# plugV15-smd.net
KiCad netlist of a schematic drawn in EAGLE
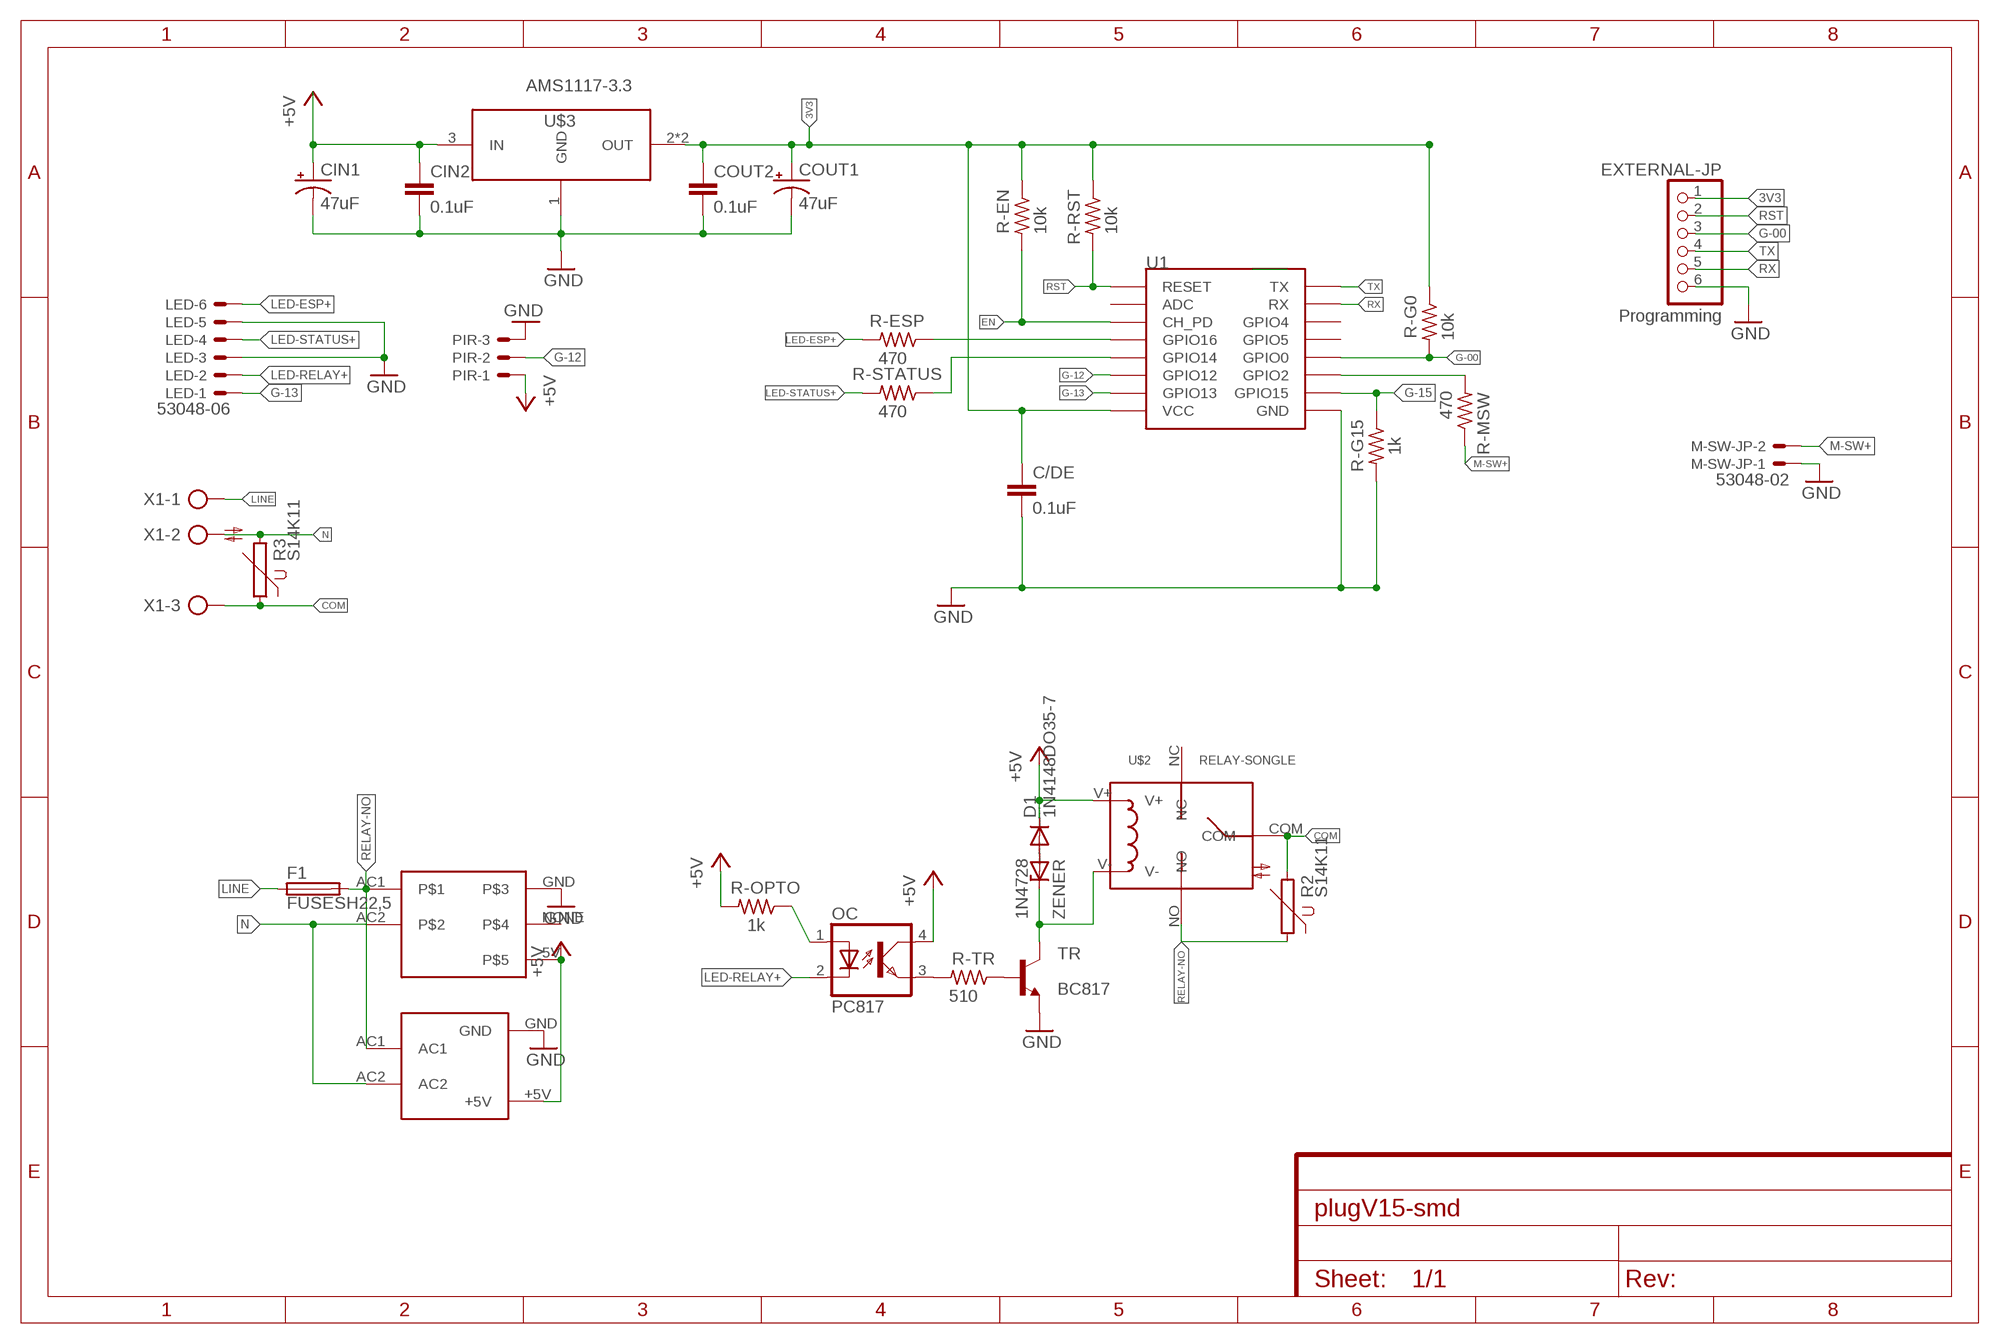
[diagram p0: schematic, sheet 1]

(export (version "E")
  (design (tool "Eeschema 10.0.6"))
  (components
    (comp (ref "C/DE")
      (value "0.1uF")
      (footprint "eagle-import:C0805")
      (libsource (lib "eagle-import") (part "C-EUC0805"))
    )
    (comp (ref "CIN1")
      (value "47uF")
      (footprint "eagle-import:E2,5-5")
      (libsource (lib "eagle-import") (part "CPOL-USE2.5-5"))
    )
    (comp (ref "CIN2")
      (value "0.1uF")
      (footprint "eagle-import:C0805")
      (libsource (lib "eagle-import") (part "C-EUC0805"))
    )
    (comp (ref "COUT1")
      (value "47uF")
      (footprint "eagle-import:E2,5-5")
      (libsource (lib "eagle-import") (part "CPOL-USE2.5-5"))
    )
    (comp (ref "COUT2")
      (value "0.1uF")
      (footprint "eagle-import:C0805")
      (libsource (lib "eagle-import") (part "C-EUC0805"))
    )
    (comp (ref "D1")
      (value "1N4148DO35-7")
      (footprint "eagle-import:DO35-7")
      (libsource (lib "eagle-import") (part "1N4148DO35-7"))
    )
    (comp (ref "EXTERNAL-JP")
      (value "Programming")
      (footprint "eagle-import:1X06")
      (libsource (lib "eagle-import") (part "PINHD-1X6"))
    )
    (comp (ref "F1")
      (value "FUSESH22,5")
      (footprint "eagle-import:SH22,5")
      (libsource (lib "eagle-import") (part "FUSESH22,5"))
    )
    (comp (ref "LED")
      (value "53048-06")
      (footprint "eagle-import:53048-06")
      (fields (field (name "MF") "WALDOM/MOLEX") (field (name "MPN") "53048-0610"))
      (libsource (lib "eagle-import") (part "53?-06048"))
    )
    (comp (ref "M-SW-JP")
      (value "53048-02")
      (footprint "eagle-import:53048-02")
      (fields (field (name "MF") "MOLEX") (field (name "MPN") "53048-0210"))
      (libsource (lib "eagle-import") (part "53?-02048"))
    )
    (comp (ref "OC")
      (value "PC817")
      (footprint "eagle-import:DIL04")
      (fields (field (name "MPN") "PC817X4J000F"))
      (libsource (lib "eagle-import") (part "PC817"))
    )
    (comp (ref "PIR")
      (value "53048-03")
      (footprint "eagle-import:53048-03")
      (fields (field (name "MF") "WALDOM/MOLEX") (field (name "MPN") "53048-0310"))
      (libsource (lib "eagle-import") (part "53?-03048"))
    )
    (comp (ref "R-EN")
      (value "10k")
      (footprint "eagle-import:M0805")
      (libsource (lib "eagle-import") (part "R-US_M0805"))
    )
    (comp (ref "R-ESP")
      (value "470")
      (footprint "eagle-import:M0805")
      (libsource (lib "eagle-import") (part "R-US_M0805"))
    )
    (comp (ref "R-G0")
      (value "10k")
      (footprint "eagle-import:M0805")
      (libsource (lib "eagle-import") (part "R-US_M0805"))
    )
    (comp (ref "R-G15")
      (value "1k")
      (footprint "eagle-import:M0805")
      (libsource (lib "eagle-import") (part "R-US_M0805"))
    )
    (comp (ref "R-MSW")
      (value "470")
      (footprint "eagle-import:M0805")
      (libsource (lib "eagle-import") (part "R-US_M0805"))
    )
    (comp (ref "R-OPTO")
      (value "1k")
      (footprint "eagle-import:M0805")
      (libsource (lib "eagle-import") (part "R-US_M0805"))
    )
    (comp (ref "R-RST")
      (value "10k")
      (footprint "eagle-import:M0805")
      (libsource (lib "eagle-import") (part "R-US_M0805"))
    )
    (comp (ref "R-STATUS")
      (value "470")
      (footprint "eagle-import:M0805")
      (libsource (lib "eagle-import") (part "R-US_M0805"))
    )
    (comp (ref "R-TR")
      (value "510")
      (footprint "eagle-import:M0805")
      (libsource (lib "eagle-import") (part "R-US_M0805"))
    )
    (comp (ref "R2")
      (value "S14K11")
      (footprint "eagle-import:S14K11")
      (libsource (lib "eagle-import") (part "S14K11"))
    )
    (comp (ref "R3")
      (value "S14K11")
      (footprint "eagle-import:S14K11")
      (libsource (lib "eagle-import") (part "S14K11"))
    )
    (comp (ref "TR")
      (value "BC817")
      (footprint "eagle-import:SOT23-BEC")
      (libsource (lib "eagle-import") (part "BC817SMD-16"))
    )
    (comp (ref "U$1")
      (value "HLK-PM01")
      (footprint "eagle-import:HLK-PM01")
      (libsource (lib "eagle-import") (part "HLK-PM01"))
    )
    (comp (ref "U$2")
      (value "RELAY-SONGLE")
      (footprint "eagle-import:RELAY-SONGLE")
      (libsource (lib "eagle-import") (part "RELAY-SONGLE"))
    )
    (comp (ref "U$3")
      (value "AMS1117-3.3")
      (footprint "eagle-import:SOT-223")
      (libsource (lib "eagle-import") (part "AMS1117-3.3"))
    )
    (comp (ref "U$4")
      (value "POWERSUPPLY-5V-700MA")
      (footprint "eagle-import:POWERSUPPLY-5V-700MA")
      (libsource (lib "eagle-import") (part "POWERSUPPLY-5V-700MA"))
    )
    (comp (ref "U1")
      (value "ESP12SMD")
      (footprint "eagle-import:ESP12-SMD")
      (libsource (lib "eagle-import") (part "ESP12SMD"))
    )
    (comp (ref "X1")
      (value "AK300/3")
      (footprint "eagle-import:AK300_3")
      (libsource (lib "eagle-import") (part "AK300/3"))
    )
    (comp (ref "ZENER")
      (value "1N4728")
      (footprint "eagle-import:DO41Z10")
      (libsource (lib "eagle-import") (part "1N4728"))
    )
  )
  (nets
    (net (code "1") (name "+5V") (class "Default")
      (node (ref "CIN1") (pin "+") (pinfunction "+_+") (pintype "passive"))
      (node (ref "CIN2") (pin "1") (pinfunction "1_1") (pintype "passive"))
      (node (ref "D1") (pin "C") (pinfunction "C_C") (pintype "passive"))
      (node (ref "OC") (pin "4") (pinfunction "COL_4") (pintype "passive"))
      (node (ref "PIR") (pin "1") (pinfunction "S_1") (pintype "passive"))
      (node (ref "R-OPTO") (pin "2") (pinfunction "2_2") (pintype "passive"))
      (node (ref "U$1") (pin "+5V") (pinfunction "+5V_+5V") (pintype "bidirectional"))
      (node (ref "U$2") (pin "V+") (pinfunction "V+_V+") (pintype "bidirectional"))
      (node (ref "U$3") (pin "3") (pinfunction "IN_3") (pintype "input"))
      (node (ref "U$4") (pin "5V") (pinfunction "P$5_5V") (pintype "bidirectional"))
    )
    (net (code "2") (name "3V3") (class "Default")
      (node (ref "C/DE") (pin "1") (pinfunction "1_1") (pintype "passive"))
      (node (ref "COUT1") (pin "+") (pinfunction "+_+") (pintype "passive"))
      (node (ref "COUT2") (pin "1") (pinfunction "1_1") (pintype "passive"))
      (node (ref "EXTERNAL-JP") (pin "1") (pinfunction "1_1") (pintype "passive"))
      (node (ref "R-EN") (pin "1") (pinfunction "1_1") (pintype "passive"))
      (node (ref "R-G0") (pin "1") (pinfunction "1_1") (pintype "passive"))
      (node (ref "R-RST") (pin "1") (pinfunction "1_1") (pintype "passive"))
      (node (ref "U$3") (pin "2") (pinfunction "OUT_2") (pintype "output"))
      (node (ref "U$3") (pin "4") (pinfunction "OUT_4") (pintype "output"))
      (node (ref "U1") (pin "VCC") (pinfunction "VCC_VCC") (pintype "bidirectional"))
    )
    (net (code "3") (name "COM") (class "Default")
      (node (ref "R2") (pin "2") (pinfunction "2_2") (pintype "passive"))
      (node (ref "R3") (pin "1") (pinfunction "1_1") (pintype "passive"))
      (node (ref "U$2") (pin "COM") (pinfunction "COM_COM") (pintype "bidirectional"))
      (node (ref "X1") (pin "3") (pinfunction "KL_3") (pintype "passive"))
    )
    (net (code "4") (name "EN") (class "Default")
      (node (ref "R-EN") (pin "2") (pinfunction "2_2") (pintype "passive"))
      (node (ref "U1") (pin "CH_PD") (pinfunction "CH_PD_CH_PD") (pintype "bidirectional"))
    )
    (net (code "5") (name "G-00") (class "Default")
      (node (ref "EXTERNAL-JP") (pin "3") (pinfunction "3_3") (pintype "passive"))
      (node (ref "R-G0") (pin "2") (pinfunction "2_2") (pintype "passive"))
      (node (ref "U1") (pin "GPIO0") (pinfunction "GPIO0_GPIO0") (pintype "bidirectional"))
    )
    (net (code "6") (name "G-12") (class "Default")
      (node (ref "PIR") (pin "2") (pinfunction "S_2") (pintype "passive"))
      (node (ref "U1") (pin "GPIO12") (pinfunction "GPIO12_GPIO12") (pintype "bidirectional"))
    )
    (net (code "7") (name "G-13") (class "Default")
      (node (ref "LED") (pin "1") (pinfunction "S_1") (pintype "passive"))
      (node (ref "U1") (pin "GPIO13") (pinfunction "GPIO13_GPIO13") (pintype "bidirectional"))
    )
    (net (code "8") (name "G-15") (class "Default")
      (node (ref "R-G15") (pin "1") (pinfunction "1_1") (pintype "passive"))
      (node (ref "U1") (pin "GPIO15") (pinfunction "GPIO15_GPIO15") (pintype "bidirectional"))
    )
    (net (code "9") (name "GND") (class "Default")
      (node (ref "C/DE") (pin "2") (pinfunction "2_2") (pintype "passive"))
      (node (ref "CIN1") (pin "-") (pinfunction "-_-") (pintype "passive"))
      (node (ref "CIN2") (pin "2") (pinfunction "2_2") (pintype "passive"))
      (node (ref "COUT1") (pin "-") (pinfunction "-_-") (pintype "passive"))
      (node (ref "COUT2") (pin "2") (pinfunction "2_2") (pintype "passive"))
      (node (ref "EXTERNAL-JP") (pin "6") (pinfunction "6_6") (pintype "passive"))
      (node (ref "LED") (pin "3") (pinfunction "S_3") (pintype "passive"))
      (node (ref "LED") (pin "5") (pinfunction "S_5") (pintype "passive"))
      (node (ref "M-SW-JP") (pin "1") (pinfunction "S_1") (pintype "passive"))
      (node (ref "PIR") (pin "3") (pinfunction "S_3") (pintype "passive"))
      (node (ref "R-G15") (pin "2") (pinfunction "2_2") (pintype "passive"))
      (node (ref "TR") (pin "E") (pinfunction "E_E") (pintype "passive"))
      (node (ref "U$1") (pin "GND") (pinfunction "GND_GND") (pintype "bidirectional"))
      (node (ref "U$3") (pin "1") (pinfunction "GND_1") (pintype "passive"))
      (node (ref "U$4") (pin "GND") (pinfunction "P$3_GND") (pintype "bidirectional"))
      (node (ref "U1") (pin "GND") (pinfunction "GND_GND") (pintype "bidirectional"))
    )
    (net (code "10") (name "LED-ESP+") (class "Default")
      (node (ref "LED") (pin "6") (pinfunction "S_6") (pintype "passive"))
      (node (ref "R-ESP") (pin "2") (pinfunction "2_2") (pintype "passive"))
    )
    (net (code "11") (name "LED-RELAY+") (class "Default")
      (node (ref "LED") (pin "2") (pinfunction "S_2") (pintype "passive"))
      (node (ref "OC") (pin "2") (pinfunction "C_2") (pintype "passive"))
    )
    (net (code "12") (name "LED-STATUS+") (class "Default")
      (node (ref "LED") (pin "4") (pinfunction "S_4") (pintype "passive"))
      (node (ref "R-STATUS") (pin "2") (pinfunction "2_2") (pintype "passive"))
    )
    (net (code "13") (name "LINE") (class "Default")
      (node (ref "F1") (pin "1") (pinfunction "1_1") (pintype "passive"))
      (node (ref "X1") (pin "1") (pinfunction "KL_1") (pintype "passive"))
    )
    (net (code "14") (name "M-SW+") (class "Default")
      (node (ref "M-SW-JP") (pin "2") (pinfunction "S_2") (pintype "passive"))
      (node (ref "R-MSW") (pin "1") (pinfunction "1_1") (pintype "passive"))
    )
    (net (code "15") (name "N") (class "Default")
      (node (ref "R3") (pin "2") (pinfunction "2_2") (pintype "passive"))
      (node (ref "U$1") (pin "AC2") (pinfunction "AC2_AC2") (pintype "bidirectional"))
      (node (ref "U$4") (pin "AC2") (pinfunction "P$2_AC2") (pintype "bidirectional"))
      (node (ref "X1") (pin "2") (pinfunction "KL_2") (pintype "passive"))
    )
    (net (code "16") (name "Net-(D1-PadA)") (class "Default")
      (node (ref "D1") (pin "A") (pinfunction "A_A") (pintype "passive"))
      (node (ref "ZENER") (pin "A") (pinfunction "A_A") (pintype "passive"))
    )
    (net (code "17") (name "Net-(OC-A)") (class "Default")
      (node (ref "OC") (pin "1") (pinfunction "A_1") (pintype "passive"))
      (node (ref "R-OPTO") (pin "1") (pinfunction "1_1") (pintype "passive"))
    )
    (net (code "18") (name "Net-(OC-EMIT)") (class "Default")
      (node (ref "OC") (pin "3") (pinfunction "EMIT_3") (pintype "passive"))
      (node (ref "R-TR") (pin "2") (pinfunction "2_2") (pintype "passive"))
    )
    (net (code "19") (name "Net-(R-ESP-Pad1)") (class "Default")
      (node (ref "R-ESP") (pin "1") (pinfunction "1_1") (pintype "passive"))
      (node (ref "U1") (pin "GPIO16") (pinfunction "GPIO16_GPIO16") (pintype "bidirectional"))
    )
    (net (code "20") (name "Net-(R-MSW-Pad2)") (class "Default")
      (node (ref "R-MSW") (pin "2") (pinfunction "2_2") (pintype "passive"))
      (node (ref "U1") (pin "GPIO2") (pinfunction "GPIO2_GPIO2") (pintype "bidirectional"))
    )
    (net (code "21") (name "Net-(R-STATUS-Pad1)") (class "Default")
      (node (ref "R-STATUS") (pin "1") (pinfunction "1_1") (pintype "passive"))
      (node (ref "U1") (pin "GPIO14") (pinfunction "GPIO14_GPIO14") (pintype "bidirectional"))
    )
    (net (code "22") (name "Net-(R-TR-Pad1)") (class "Default")
      (node (ref "R-TR") (pin "1") (pinfunction "1_1") (pintype "passive"))
      (node (ref "TR") (pin "B") (pinfunction "B_B") (pintype "passive"))
    )
    (net (code "23") (name "Net-(TR-PadC)") (class "Default")
      (node (ref "TR") (pin "C") (pinfunction "C_C") (pintype "passive"))
      (node (ref "U$2") (pin "V-") (pinfunction "V-_V-") (pintype "bidirectional"))
      (node (ref "ZENER") (pin "C") (pinfunction "C_C") (pintype "passive"))
    )
    (net (code "24") (name "RELAY-NO") (class "Default")
      (node (ref "F1") (pin "2") (pinfunction "2_2") (pintype "passive"))
      (node (ref "R2") (pin "1") (pinfunction "1_1") (pintype "passive"))
      (node (ref "U$1") (pin "AC1") (pinfunction "AC1_AC1") (pintype "bidirectional"))
      (node (ref "U$2") (pin "NO") (pinfunction "NO_NO") (pintype "bidirectional"))
      (node (ref "U$4") (pin "AC1") (pinfunction "P$1_AC1") (pintype "bidirectional"))
    )
    (net (code "25") (name "RST") (class "Default")
      (node (ref "EXTERNAL-JP") (pin "2") (pinfunction "2_2") (pintype "passive"))
      (node (ref "R-RST") (pin "2") (pinfunction "2_2") (pintype "passive"))
      (node (ref "U1") (pin "RESET") (pinfunction "RESET_RESET") (pintype "bidirectional"))
    )
    (net (code "26") (name "RX") (class "Default")
      (node (ref "EXTERNAL-JP") (pin "5") (pinfunction "5_5") (pintype "passive"))
      (node (ref "U1") (pin "RXD0") (pinfunction "RX_RXD0") (pintype "bidirectional"))
    )
    (net (code "27") (name "TX") (class "Default")
      (node (ref "EXTERNAL-JP") (pin "4") (pinfunction "4_4") (pintype "passive"))
      (node (ref "U1") (pin "TXD0") (pinfunction "TX_TXD0") (pintype "bidirectional"))
    )
    (net (code "28") (name "unconnected-(U$2-PadNC)") (class "Default")
      (node (ref "U$2") (pin "NC") (pinfunction "NC_NC") (pintype "bidirectional"))
    )
    (net (code "29") (name "unconnected-(U$4-P$4-PadNONE)") (class "Default")
      (node (ref "U$4") (pin "NONE") (pinfunction "P$4_NONE") (pintype "bidirectional"))
    )
    (net (code "30") (name "unconnected-(U1-PadADC)") (class "Default")
      (node (ref "U1") (pin "ADC") (pinfunction "ADC_ADC") (pintype "bidirectional"))
    )
    (net (code "31") (name "unconnected-(U1-PadGPIO4)") (class "Default")
      (node (ref "U1") (pin "GPIO4") (pinfunction "GPIO4_GPIO4") (pintype "bidirectional"))
    )
    (net (code "32") (name "unconnected-(U1-PadGPIO5)") (class "Default")
      (node (ref "U1") (pin "GPIO5") (pinfunction "GPIO5_GPIO5") (pintype "bidirectional"))
    )
  )
)
